# TLE5010.net
KiCad netlist of a schematic drawn in EAGLE
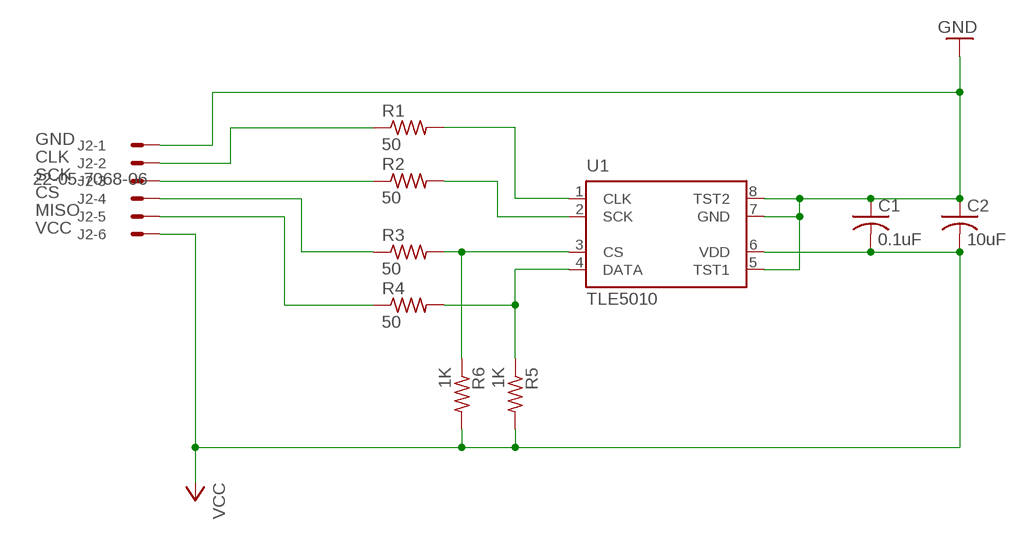
[diagram p0: schematic, sheet 1]

(export (version "E")
  (design (tool "Eeschema 10.0.6"))
  (components
    (comp (ref "C1")
      (value "0.1uF")
      (footprint "eagle-import:C1206")
      (libsource (lib "eagle-import") (part "C-USC1206"))
    )
    (comp (ref "C2")
      (value "10uF")
      (footprint "eagle-import:C1206")
      (libsource (lib "eagle-import") (part "C-USC1206"))
    )
    (comp (ref "J2")
      (value "22-05-7068-06")
      (footprint "eagle-import:7395-06")
      (fields (field (name "MF") "MOLEX"))
      (libsource (lib "eagle-import") (part "22-?-0605-7068"))
    )
    (comp (ref "R1")
      (value "50")
      (footprint "eagle-import:R1206")
      (libsource (lib "eagle-import") (part "R-US_R1206"))
    )
    (comp (ref "R2")
      (value "50")
      (footprint "eagle-import:R1206")
      (libsource (lib "eagle-import") (part "R-US_R1206"))
    )
    (comp (ref "R3")
      (value "50")
      (footprint "eagle-import:R1206")
      (libsource (lib "eagle-import") (part "R-US_R1206"))
    )
    (comp (ref "R4")
      (value "50")
      (footprint "eagle-import:R1206")
      (libsource (lib "eagle-import") (part "R-US_R1206"))
    )
    (comp (ref "R5")
      (value "1K")
      (footprint "eagle-import:R1206")
      (libsource (lib "eagle-import") (part "R-US_R1206"))
    )
    (comp (ref "R6")
      (value "1K")
      (footprint "eagle-import:R1206")
      (libsource (lib "eagle-import") (part "R-US_R1206"))
    )
    (comp (ref "U1")
      (value "TLE5010")
      (footprint "eagle-import:PG-DSO-8")
      (libsource (lib "eagle-import") (part "TLE5010"))
    )
  )
  (nets
    (net (code "1") (name "/CLK") (class "Default")
      (node (ref "J2") (pin "2") (pinfunction "S_2") (pintype "passive"))
      (node (ref "R1") (pin "1") (pinfunction "1_1") (pintype "passive"))
    )
    (net (code "2") (name "/CS") (class "Default")
      (node (ref "J2") (pin "4") (pinfunction "S_4") (pintype "passive"))
      (node (ref "R3") (pin "1") (pinfunction "1_1") (pintype "passive"))
    )
    (net (code "3") (name "/MISO") (class "Default")
      (node (ref "J2") (pin "5") (pinfunction "S_5") (pintype "passive"))
      (node (ref "R4") (pin "1") (pinfunction "1_1") (pintype "passive"))
    )
    (net (code "4") (name "/SCK") (class "Default")
      (node (ref "J2") (pin "3") (pinfunction "S_3") (pintype "passive"))
      (node (ref "R2") (pin "1") (pinfunction "1_1") (pintype "passive"))
    )
    (net (code "5") (name "GND") (class "Default")
      (node (ref "C1") (pin "1") (pinfunction "1_1") (pintype "passive"))
      (node (ref "C2") (pin "1") (pinfunction "1_1") (pintype "passive"))
      (node (ref "J2") (pin "1") (pinfunction "S_1") (pintype "passive"))
      (node (ref "U1") (pin "5") (pinfunction "TST1_5") (pintype "bidirectional"))
      (node (ref "U1") (pin "7") (pinfunction "GND_7") (pintype "power_in"))
      (node (ref "U1") (pin "8") (pinfunction "TST2_8") (pintype "bidirectional"))
    )
    (net (code "6") (name "Net-(U1-CLK)") (class "Default")
      (node (ref "R1") (pin "2") (pinfunction "2_2") (pintype "passive"))
      (node (ref "U1") (pin "1") (pinfunction "CLK_1") (pintype "input"))
    )
    (net (code "7") (name "Net-(U1-CS)") (class "Default")
      (node (ref "R3") (pin "2") (pinfunction "2_2") (pintype "passive"))
      (node (ref "R6") (pin "1") (pinfunction "1_1") (pintype "passive"))
      (node (ref "U1") (pin "3") (pinfunction "CS_3") (pintype "input"))
    )
    (net (code "8") (name "Net-(U1-DATA)") (class "Default")
      (node (ref "R4") (pin "2") (pinfunction "2_2") (pintype "passive"))
      (node (ref "R5") (pin "1") (pinfunction "1_1") (pintype "passive"))
      (node (ref "U1") (pin "4") (pinfunction "DATA_4") (pintype "bidirectional"))
    )
    (net (code "9") (name "Net-(U1-SCK)") (class "Default")
      (node (ref "R2") (pin "2") (pinfunction "2_2") (pintype "passive"))
      (node (ref "U1") (pin "2") (pinfunction "SCK_2") (pintype "input"))
    )
    (net (code "10") (name "VCC") (class "Default")
      (node (ref "C1") (pin "2") (pinfunction "2_2") (pintype "passive"))
      (node (ref "C2") (pin "2") (pinfunction "2_2") (pintype "passive"))
      (node (ref "J2") (pin "6") (pinfunction "S_6") (pintype "passive"))
      (node (ref "R5") (pin "2") (pinfunction "2_2") (pintype "passive"))
      (node (ref "R6") (pin "2") (pinfunction "2_2") (pintype "passive"))
      (node (ref "U1") (pin "6") (pinfunction "VDD_6") (pintype "power_in"))
    )
  )
)
